# SFP.net
KiCad netlist of a schematic drawn in Altium Designer
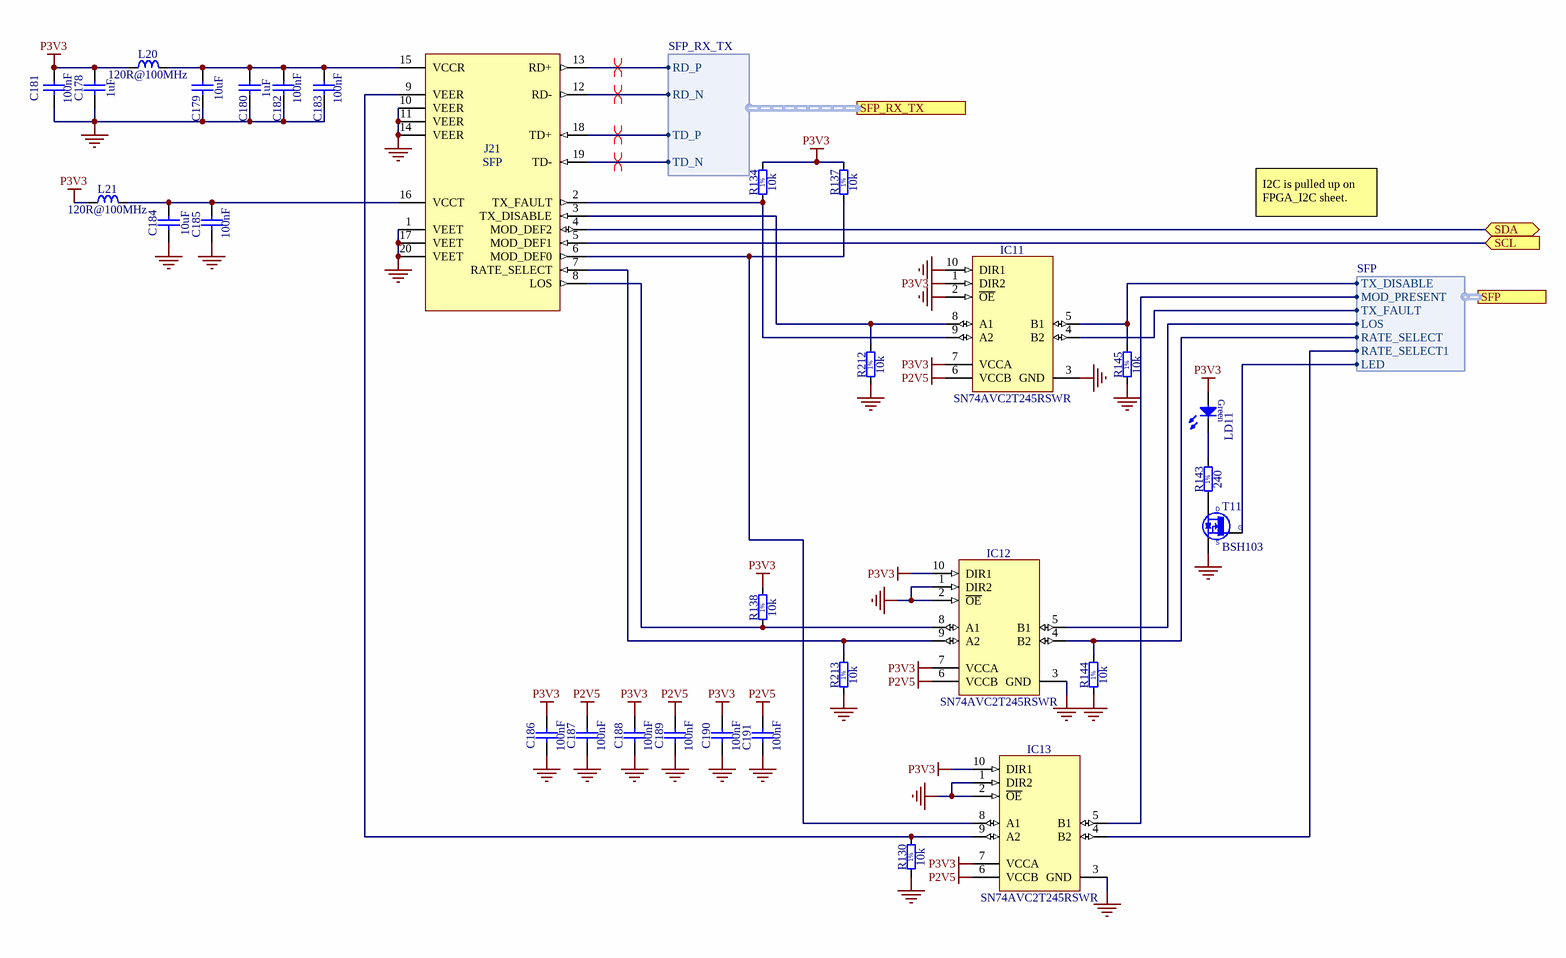
[diagram p0: SFP.SchDoc]

(export (version "E")
  (design (tool "Eeschema 10.0.6"))
  (components
    (comp (ref "C178")
      (value "1uF")
      (footprint "CAPC1005X55N")
      (description "Non-polarised capacitor")
      (fields
        (field (name "PART NUMBER") "CC0402_1UF_16V_10%_X5R")
        (field (name "VOLTAGE") "16V")
        (field (name "AUTHOR") "CERN DEM JLC")
      )
      (libsource (lib "Capacitors") (part "Capacitor - non polarized"))
    )
    (comp (ref "C179")
      (value "10uF")
      (footprint "CAPC2012X95N")
      (description "Non-polarised capacitor")
      (fields
        (field (name "PART NUMBER") "CC0805_10UF_25V_10%_X5R")
        (field (name "VOLTAGE") "25V")
        (field (name "AUTHOR") "CERN DEM JLC")
      )
      (libsource (lib "Capacitors") (part "Capacitor - non polarized"))
    )
    (comp (ref "C180")
      (value "1uF")
      (footprint "CAPC1005X55N")
      (description "Non-polarised capacitor")
      (fields
        (field (name "PART NUMBER") "CC0402_1UF_16V_10%_X5R")
        (field (name "VOLTAGE") "16V")
        (field (name "AUTHOR") "CERN DEM JLC")
      )
      (libsource (lib "Capacitors") (part "Capacitor - non polarized"))
    )
    (comp (ref "C181")
      (value "100nF")
      (footprint "CAPC0603X33N")
      (description "Non-polarised capacitor")
      (fields
        (field (name "PART NUMBER") "CC0201_100NF_6.3V_10%_X5R")
        (field (name "VOLTAGE") "6.3V")
        (field (name "AUTHOR") "CERN DEM JLC")
      )
      (libsource (lib "Capacitors") (part "Capacitor - non polarized"))
    )
    (comp (ref "C182")
      (value "100nF")
      (footprint "CAPC0603X33N")
      (description "Non-polarised capacitor")
      (fields
        (field (name "PART NUMBER") "CC0201_100NF_6.3V_10%_X5R")
        (field (name "VOLTAGE") "6.3V")
        (field (name "AUTHOR") "CERN DEM JLC")
      )
      (libsource (lib "Capacitors") (part "Capacitor - non polarized"))
    )
    (comp (ref "C183")
      (value "100nF")
      (footprint "CAPC0603X33N")
      (description "Non-polarised capacitor")
      (fields
        (field (name "PART NUMBER") "CC0201_100NF_6.3V_10%_X5R")
        (field (name "VOLTAGE") "6.3V")
        (field (name "AUTHOR") "CERN DEM JLC")
      )
      (libsource (lib "Capacitors") (part "Capacitor - non polarized"))
    )
    (comp (ref "C184")
      (value "10uF")
      (footprint "CAPC2012X95N")
      (description "Non-polarised capacitor")
      (fields
        (field (name "PART NUMBER") "CC0805_10UF_25V_10%_X5R")
        (field (name "VOLTAGE") "25V")
        (field (name "AUTHOR") "CERN DEM JLC")
      )
      (libsource (lib "Capacitors") (part "Capacitor - non polarized"))
    )
    (comp (ref "C185")
      (value "100nF")
      (footprint "CAPC0603X33N")
      (description "Non-polarised capacitor")
      (fields
        (field (name "PART NUMBER") "CC0201_100NF_6.3V_10%_X5R")
        (field (name "VOLTAGE") "6.3V")
        (field (name "AUTHOR") "CERN DEM JLC")
      )
      (libsource (lib "Capacitors") (part "Capacitor - non polarized"))
    )
    (comp (ref "C186")
      (value "100nF")
      (footprint "CAPC0603X33N")
      (description "Non-polarised capacitor")
      (fields
        (field (name "PART NUMBER") "CC0201_100NF_6.3V_10%_X5R")
        (field (name "VOLTAGE") "6.3V")
        (field (name "AUTHOR") "CERN DEM JLC")
      )
      (libsource (lib "Capacitors") (part "Capacitor - non polarized"))
    )
    (comp (ref "C187")
      (value "100nF")
      (footprint "CAPC0603X33N")
      (description "Non-polarised capacitor")
      (fields
        (field (name "PART NUMBER") "CC0201_100NF_6.3V_10%_X5R")
        (field (name "VOLTAGE") "6.3V")
        (field (name "AUTHOR") "CERN DEM JLC")
      )
      (libsource (lib "Capacitors") (part "Capacitor - non polarized"))
    )
    (comp (ref "C188")
      (value "100nF")
      (footprint "CAPC0603X33N")
      (description "Non-polarised capacitor")
      (fields
        (field (name "PART NUMBER") "CC0201_100NF_6.3V_10%_X5R")
        (field (name "VOLTAGE") "6.3V")
        (field (name "AUTHOR") "CERN DEM JLC")
      )
      (libsource (lib "Capacitors") (part "Capacitor - non polarized"))
    )
    (comp (ref "C189")
      (value "100nF")
      (footprint "CAPC0603X33N")
      (description "Non-polarised capacitor")
      (fields
        (field (name "PART NUMBER") "CC0201_100NF_6.3V_10%_X5R")
        (field (name "VOLTAGE") "6.3V")
        (field (name "AUTHOR") "CERN DEM JLC")
      )
      (libsource (lib "Capacitors") (part "Capacitor - non polarized"))
    )
    (comp (ref "C190")
      (value "100nF")
      (footprint "CAPC0603X33N")
      (description "Non-polarised capacitor")
      (fields
        (field (name "PART NUMBER") "CC0201_100NF_6.3V_10%_X5R")
        (field (name "VOLTAGE") "6.3V")
        (field (name "AUTHOR") "CERN DEM JLC")
      )
      (libsource (lib "Capacitors") (part "Capacitor - non polarized"))
    )
    (comp (ref "C191")
      (value "100nF")
      (footprint "CAPC0603X33N")
      (description "Non-polarised capacitor")
      (fields
        (field (name "PART NUMBER") "CC0201_100NF_6.3V_10%_X5R")
        (field (name "VOLTAGE") "6.3V")
        (field (name "AUTHOR") "CERN DEM JLC")
      )
      (libsource (lib "Capacitors") (part "Capacitor - non polarized"))
    )
    (comp (ref "IC11")
      (value "SN74AVC2T245RSWR")
      (footprint "QFN40P140X180X55-10N")
      (description "Dual-Bit Dual-Supply Bus Transceiver With Configurable Voltage Translation and 3-State Outputs")
      (fields (field (name "MANUFACTURER") "TEXAS INSTRUMENTS") (field (name "AUTHOR") "CERN DEM JLC"))
      (libsource (lib "ICs And Semiconductors") (part "742T245"))
    )
    (comp (ref "IC12")
      (value "SN74AVC2T245RSWR")
      (footprint "QFN40P140X180X55-10N")
      (description "Dual-Bit Dual-Supply Bus Transceiver With Configurable Voltage Translation and 3-State Outputs")
      (fields (field (name "MANUFACTURER") "TEXAS INSTRUMENTS") (field (name "AUTHOR") "CERN DEM JLC"))
      (libsource (lib "ICs And Semiconductors") (part "742T245"))
    )
    (comp (ref "IC13")
      (value "SN74AVC2T245RSWR")
      (footprint "QFN40P140X180X55-10N")
      (description "Dual-Bit Dual-Supply Bus Transceiver With Configurable Voltage Translation and 3-State Outputs")
      (fields (field (name "MANUFACTURER") "TEXAS INSTRUMENTS") (field (name "AUTHOR") "CERN DEM JLC"))
      (libsource (lib "ICs And Semiconductors") (part "742T245"))
    )
    (comp (ref "J21")
      (value "SFP")
      (footprint "TYCO_1367073-1")
      (description "20 Position SFP  Connector (Small Form-factor Pluggable)")
      (fields
        (field (name "PART NUMBER") "TYCO_1367073-1")
        (field (name "MANUFACTURER") "TYCO ELECTRONICS")
        (field (name "AUTHOR") "CERN DEM JLC")
      )
      (libsource (lib "Connectors") (part "SFPx1"))
    )
    (comp (ref "L20")
      (value "120R@100MHz")
      (footprint "INDC1608X65N")
      (description "Inductor")
      (fields
        (field (name "PART NUMBER") "IND0603_MURATA_BLM18SG121TN1D")
        (field (name "POWER") "3A")
        (field (name "AUTHOR") "CERN DEM JLC")
      )
      (libsource (lib "Inductors & Transformers") (part "Inductor"))
    )
    (comp (ref "L21")
      (value "120R@100MHz")
      (footprint "INDC1608X65N")
      (description "Inductor")
      (fields
        (field (name "PART NUMBER") "IND0603_MURATA_BLM18SG121TN1D")
        (field (name "POWER") "3A")
        (field (name "AUTHOR") "CERN DEM JLC")
      )
      (libsource (lib "Inductors & Transformers") (part "Inductor"))
    )
    (comp (ref "LD11")
      (value "Green")
      (footprint "LED_AVAGO_HSME-C120")
      (description "LED Green 1C 2A")
      (fields
        (field (name "PART NUMBER") "LED_AVAGO_HSME-C120")
        (field (name "MANUFACTURER") "AVAGO TECHNOLOGIES")
        (field (name "AUTHOR") "CERN DEM JMW")
      )
      (libsource (lib "ICs And Semiconductors") (part "LED Green 1C 2A"))
    )
    (comp (ref "R130")
      (value "10k")
      (footprint "RESC1005X40N")
      (description "Resistor - 1%")
      (fields
        (field (name "PART NUMBER") "R0402_10K_1%_0.0625W_100PPM")
        (field (name "POWER") "0.0625W")
        (field (name "AUTHOR") "CERN DEM JLC")
      )
      (libsource (lib "Resistors") (part "Resistor - 1%"))
    )
    (comp (ref "R134")
      (value "10k")
      (footprint "RESC1005X40N")
      (description "Resistor - 1%")
      (fields
        (field (name "PART NUMBER") "R0402_10K_1%_0.0625W_100PPM")
        (field (name "POWER") "0.0625W")
        (field (name "AUTHOR") "CERN DEM JLC")
      )
      (libsource (lib "Resistors") (part "Resistor - 1%"))
    )
    (comp (ref "R137")
      (value "10k")
      (footprint "RESC1005X40N")
      (description "Resistor - 1%")
      (fields
        (field (name "PART NUMBER") "R0402_10K_1%_0.0625W_100PPM")
        (field (name "POWER") "0.0625W")
        (field (name "AUTHOR") "CERN DEM JLC")
      )
      (libsource (lib "Resistors") (part "Resistor - 1%"))
    )
    (comp (ref "R138")
      (value "10k")
      (footprint "RESC1005X40N")
      (description "Resistor - 1%")
      (fields
        (field (name "PART NUMBER") "R0402_10K_1%_0.0625W_100PPM")
        (field (name "POWER") "0.0625W")
        (field (name "AUTHOR") "CERN DEM JLC")
      )
      (libsource (lib "Resistors") (part "Resistor - 1%"))
    )
    (comp (ref "R143")
      (value "240")
      (footprint "RESC1005X40N")
      (description "Resistor - 1%")
      (fields
        (field (name "PART NUMBER") "R0402_240R_1%_0.0625W_100PPM")
        (field (name "POWER") "0.0625W")
        (field (name "AUTHOR") "CERN DEM JLC")
      )
      (libsource (lib "Resistors") (part "Resistor - 1%"))
    )
    (comp (ref "R144")
      (value "10k")
      (footprint "RESC1005X40N")
      (description "Resistor - 1%")
      (fields
        (field (name "PART NUMBER") "R0402_10K_1%_0.0625W_100PPM")
        (field (name "POWER") "0.0625W")
        (field (name "AUTHOR") "CERN DEM JLC")
      )
      (libsource (lib "Resistors") (part "Resistor - 1%"))
    )
    (comp (ref "R145")
      (value "10k")
      (footprint "RESC1005X40N")
      (description "Resistor - 1%")
      (fields
        (field (name "PART NUMBER") "R0402_10K_1%_0.0625W_100PPM")
        (field (name "POWER") "0.0625W")
        (field (name "AUTHOR") "CERN DEM JLC")
      )
      (libsource (lib "Resistors") (part "Resistor - 1%"))
    )
    (comp (ref "R212")
      (value "10k")
      (footprint "RESC1005X40N")
      (description "Resistor - 1%")
      (fields
        (field (name "PART NUMBER") "R0402_10K_1%_0.0625W_100PPM")
        (field (name "POWER") "0.0625W")
        (field (name "AUTHOR") "CERN DEM JLC")
      )
      (libsource (lib "Resistors") (part "Resistor - 1%"))
    )
    (comp (ref "R213")
      (value "10k")
      (footprint "RESC1005X40N")
      (description "Resistor - 1%")
      (fields
        (field (name "PART NUMBER") "R0402_10K_1%_0.0625W_100PPM")
        (field (name "POWER") "0.0625W")
        (field (name "AUTHOR") "CERN DEM JLC")
      )
      (libsource (lib "Resistors") (part "Resistor - 1%"))
    )
    (comp (ref "T11")
      (value "BSH103")
      (footprint "SOT95P230X110-3N")
      (description "N-CHANNEL MOSFET WITH DIODE")
      (fields (field (name "MANUFACTURER") "NEXPERIA") (field (name "AUTHOR") "CERN DEM JLC"))
      (libsource (lib "ICs And Semiconductors") (part "N-MOSFET-D 1G 2S 3D"))
    )
  )
  (nets
    (net (code "3") (name "/LED") (class "Default")
      (node (ref "T11") (pin "1") (pinfunction "G_1") (pintype "passive"))
    )
    (net (code "4") (name "/LOS") (class "Default")
      (node (ref "IC12") (pin "5") (pinfunction "B1_5") (pintype "bidirectional"))
    )
    (net (code "5") (name "/MOD_PRESENT") (class "Default")
      (node (ref "IC13") (pin "5") (pinfunction "B1_5") (pintype "bidirectional"))
    )
    (net (code "6") (name "/RATE_SELECT") (class "Default")
      (node (ref "IC12") (pin "4") (pinfunction "B2_4") (pintype "bidirectional"))
      (node (ref "R144") (pin "2") (pinfunction "2_2") (pintype "passive"))
    )
    (net (code "7") (name "/RATE_SELECT1") (class "Default")
      (node (ref "IC13") (pin "4") (pinfunction "B2_4") (pintype "bidirectional"))
    )
    (net (code "8") (name "/RD_N") (class "Default")
      (node (ref "J21") (pin "12") (pinfunction "RD-_12") (pintype "output"))
    )
    (net (code "9") (name "/RD_P") (class "Default")
      (node (ref "J21") (pin "13") (pinfunction "RD+_13") (pintype "output"))
    )
    (net (code "10") (name "/SCL") (class "Default")
      (node (ref "J21") (pin "5") (pinfunction "MOD_DEF1_5") (pintype "input"))
    )
    (net (code "11") (name "/SDA") (class "Default")
      (node (ref "J21") (pin "4") (pinfunction "MOD_DEF2_4") (pintype "bidirectional"))
    )
    (net (code "12") (name "/TD_N") (class "Default")
      (node (ref "J21") (pin "19") (pinfunction "TD-_19") (pintype "input"))
    )
    (net (code "13") (name "/TD_P") (class "Default")
      (node (ref "J21") (pin "18") (pinfunction "TD+_18") (pintype "input"))
    )
    (net (code "14") (name "/TX_DISABLE") (class "Default")
      (node (ref "IC11") (pin "5") (pinfunction "B1_5") (pintype "bidirectional"))
      (node (ref "R145") (pin "2") (pinfunction "2_2") (pintype "passive"))
    )
    (net (code "15") (name "/TX_FAULT") (class "Default")
      (node (ref "IC11") (pin "4") (pinfunction "B2_4") (pintype "bidirectional"))
    )
    (net (code "18") (name "GND") (class "Default")
      (node (ref "C178") (pin "1") (pinfunction "1_1") (pintype "passive"))
      (node (ref "C179") (pin "1") (pinfunction "1_1") (pintype "passive"))
      (node (ref "C180") (pin "1") (pinfunction "1_1") (pintype "passive"))
      (node (ref "C181") (pin "1") (pinfunction "1_1") (pintype "passive"))
      (node (ref "C182") (pin "1") (pinfunction "1_1") (pintype "passive"))
      (node (ref "C183") (pin "1") (pinfunction "1_1") (pintype "passive"))
      (node (ref "C184") (pin "1") (pinfunction "1_1") (pintype "passive"))
      (node (ref "C185") (pin "1") (pinfunction "1_1") (pintype "passive"))
      (node (ref "C186") (pin "1") (pinfunction "1_1") (pintype "passive"))
      (node (ref "C187") (pin "1") (pinfunction "1_1") (pintype "passive"))
      (node (ref "C188") (pin "1") (pinfunction "1_1") (pintype "passive"))
      (node (ref "C189") (pin "1") (pinfunction "1_1") (pintype "passive"))
      (node (ref "C190") (pin "1") (pinfunction "1_1") (pintype "passive"))
      (node (ref "C191") (pin "1") (pinfunction "1_1") (pintype "passive"))
      (node (ref "IC11") (pin "10") (pinfunction "DIR1_10") (pintype "input"))
      (node (ref "IC11") (pin "2") (pinfunction "~{OE}_2") (pintype "input"))
      (node (ref "IC11") (pin "3") (pinfunction "GND_3") (pintype "power_in"))
      (node (ref "IC12") (pin "1") (pinfunction "DIR2_1") (pintype "input"))
      (node (ref "IC12") (pin "2") (pinfunction "~{OE}_2") (pintype "input"))
      (node (ref "IC12") (pin "3") (pinfunction "GND_3") (pintype "power_in"))
      (node (ref "IC13") (pin "1") (pinfunction "DIR2_1") (pintype "input"))
      (node (ref "IC13") (pin "2") (pinfunction "~{OE}_2") (pintype "input"))
      (node (ref "IC13") (pin "3") (pinfunction "GND_3") (pintype "power_in"))
      (node (ref "J21") (pin "1") (pinfunction "VEET_1") (pintype "power_in"))
      (node (ref "J21") (pin "10") (pinfunction "VEER_10") (pintype "power_in"))
      (node (ref "J21") (pin "11") (pinfunction "VEER_11") (pintype "power_in"))
      (node (ref "J21") (pin "14") (pinfunction "VEER_14") (pintype "power_in"))
      (node (ref "J21") (pin "17") (pinfunction "VEET_17") (pintype "power_in"))
      (node (ref "J21") (pin "20") (pinfunction "VEET_20") (pintype "power_in"))
      (node (ref "R130") (pin "1") (pinfunction "1_1") (pintype "passive"))
      (node (ref "R144") (pin "1") (pinfunction "1_1") (pintype "passive"))
      (node (ref "R145") (pin "1") (pinfunction "1_1") (pintype "passive"))
      (node (ref "R212") (pin "1") (pinfunction "1_1") (pintype "passive"))
      (node (ref "R213") (pin "1") (pinfunction "1_1") (pintype "passive"))
      (node (ref "T11") (pin "2") (pinfunction "S_2") (pintype "passive"))
    )
    (net (code "19") (name "Net-(IC11-A1)") (class "Default")
      (node (ref "IC11") (pin "8") (pinfunction "A1_8") (pintype "bidirectional"))
      (node (ref "J21") (pin "3") (pinfunction "TX_DISABLE_3") (pintype "input"))
      (node (ref "R212") (pin "2") (pinfunction "2_2") (pintype "passive"))
    )
    (net (code "20") (name "Net-(IC11-A2)") (class "Default")
      (node (ref "IC11") (pin "9") (pinfunction "A2_9") (pintype "bidirectional"))
      (node (ref "J21") (pin "2") (pinfunction "TX_FAULT_2") (pintype "output"))
      (node (ref "R134") (pin "1") (pinfunction "1_1") (pintype "passive"))
    )
    (net (code "21") (name "Net-(IC12-A1)") (class "Default")
      (node (ref "IC12") (pin "8") (pinfunction "A1_8") (pintype "bidirectional"))
      (node (ref "J21") (pin "8") (pinfunction "LOS_8") (pintype "output"))
      (node (ref "R138") (pin "1") (pinfunction "1_1") (pintype "passive"))
    )
    (net (code "22") (name "Net-(IC12-A2)") (class "Default")
      (node (ref "IC12") (pin "9") (pinfunction "A2_9") (pintype "bidirectional"))
      (node (ref "J21") (pin "7") (pinfunction "RATE_SELECT_7") (pintype "input"))
      (node (ref "R213") (pin "2") (pinfunction "2_2") (pintype "passive"))
    )
    (net (code "23") (name "Net-(IC13-A1)") (class "Default")
      (node (ref "IC13") (pin "8") (pinfunction "A1_8") (pintype "bidirectional"))
      (node (ref "J21") (pin "6") (pinfunction "MOD_DEF0_6") (pintype "output"))
      (node (ref "R137") (pin "1") (pinfunction "1_1") (pintype "passive"))
    )
    (net (code "24") (name "Net-(IC13-A2)") (class "Default")
      (node (ref "IC13") (pin "9") (pinfunction "A2_9") (pintype "bidirectional"))
      (node (ref "J21") (pin "9") (pinfunction "VEER_9") (pintype "power_in"))
      (node (ref "R130") (pin "2") (pinfunction "2_2") (pintype "passive"))
    )
    (net (code "25") (name "Net-(J21-VCCR)") (class "Default")
      (node (ref "C179") (pin "2") (pinfunction "2_2") (pintype "passive"))
      (node (ref "C180") (pin "2") (pinfunction "2_2") (pintype "passive"))
      (node (ref "C182") (pin "2") (pinfunction "2_2") (pintype "passive"))
      (node (ref "C183") (pin "2") (pinfunction "2_2") (pintype "passive"))
      (node (ref "J21") (pin "15") (pinfunction "VCCR_15") (pintype "power_in"))
      (node (ref "L20") (pin "2") (pinfunction "2_2") (pintype "passive"))
    )
    (net (code "26") (name "Net-(J21-VCCT)") (class "Default")
      (node (ref "C184") (pin "2") (pinfunction "2_2") (pintype "passive"))
      (node (ref "C185") (pin "2") (pinfunction "2_2") (pintype "passive"))
      (node (ref "J21") (pin "16") (pinfunction "VCCT_16") (pintype "power_in"))
      (node (ref "L21") (pin "2") (pinfunction "2_2") (pintype "passive"))
    )
    (net (code "27") (name "Net-(LD11-C)") (class "Default")
      (node (ref "LD11") (pin "1") (pinfunction "C_1") (pintype "passive"))
      (node (ref "R143") (pin "2") (pinfunction "2_2") (pintype "passive"))
    )
    (net (code "28") (name "Net-(T11-D)") (class "Default")
      (node (ref "R143") (pin "1") (pinfunction "1_1") (pintype "passive"))
      (node (ref "T11") (pin "3") (pinfunction "D_3") (pintype "passive"))
    )
    (net (code "29") (name "P2V5") (class "Default")
      (node (ref "C187") (pin "2") (pinfunction "2_2") (pintype "passive"))
      (node (ref "C189") (pin "2") (pinfunction "2_2") (pintype "passive"))
      (node (ref "C191") (pin "2") (pinfunction "2_2") (pintype "passive"))
      (node (ref "IC11") (pin "6") (pinfunction "VCCB_6") (pintype "power_in"))
      (node (ref "IC12") (pin "6") (pinfunction "VCCB_6") (pintype "power_in"))
      (node (ref "IC13") (pin "6") (pinfunction "VCCB_6") (pintype "power_in"))
    )
    (net (code "30") (name "P3V3") (class "Default")
      (node (ref "C178") (pin "2") (pinfunction "2_2") (pintype "passive"))
      (node (ref "C181") (pin "2") (pinfunction "2_2") (pintype "passive"))
      (node (ref "C186") (pin "2") (pinfunction "2_2") (pintype "passive"))
      (node (ref "C188") (pin "2") (pinfunction "2_2") (pintype "passive"))
      (node (ref "C190") (pin "2") (pinfunction "2_2") (pintype "passive"))
      (node (ref "IC11") (pin "1") (pinfunction "DIR2_1") (pintype "input"))
      (node (ref "IC11") (pin "7") (pinfunction "VCCA_7") (pintype "power_in"))
      (node (ref "IC12") (pin "10") (pinfunction "DIR1_10") (pintype "input"))
      (node (ref "IC12") (pin "7") (pinfunction "VCCA_7") (pintype "power_in"))
      (node (ref "IC13") (pin "10") (pinfunction "DIR1_10") (pintype "input"))
      (node (ref "IC13") (pin "7") (pinfunction "VCCA_7") (pintype "power_in"))
      (node (ref "L20") (pin "1") (pinfunction "1_1") (pintype "passive"))
      (node (ref "L21") (pin "1") (pinfunction "1_1") (pintype "passive"))
      (node (ref "LD11") (pin "2") (pinfunction "A_2") (pintype "passive"))
      (node (ref "R134") (pin "2") (pinfunction "2_2") (pintype "passive"))
      (node (ref "R137") (pin "2") (pinfunction "2_2") (pintype "passive"))
      (node (ref "R138") (pin "2") (pinfunction "2_2") (pintype "passive"))
    )
  )
)
